# CosmoLink_Alpha_V0_00.net
KiCad netlist of a schematic drawn in Altium Designer
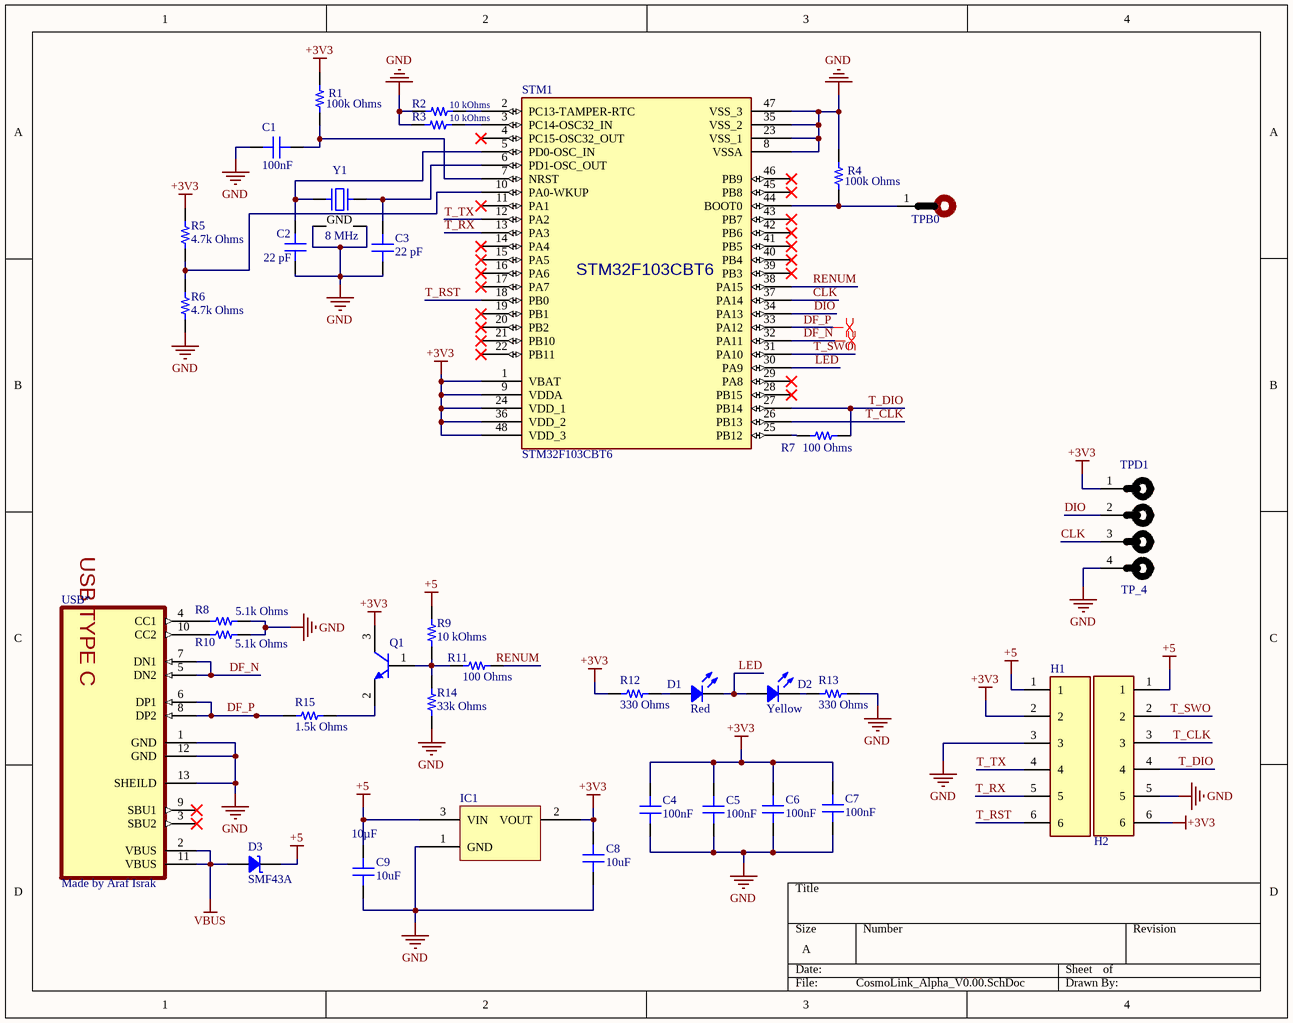
[diagram p0: CosmoLink_Alpha_V0.00.SchDoc]

(export (version "E")
  (design (tool "Eeschema 10.0.6"))
  (components
    (comp (ref "C1")
      (value "0.1µF")
      (footprint "CAP 0603_1608")
      (description "CAP CER 0.1UF 100V X7R 0603")
      (fields
        (field (name "PART NUMBER") "06031C104KAT2A")
        (field (name "CAPACITANCE") "100nF")
        (field (name "MANUFACTURER") "AVX Corporation")
      )
      (libsource (lib "Celestial Altium Library - altium_library") (part "Capacitor"))
    )
    (comp (ref "C2")
      (value "22 pF")
      (footprint "CAP 0603_1608")
      (description "HIGH-Q MLCC (CF): 0603, 22 PF (1")
      (fields
        (field (name "PART NUMBER") "C06CF220F-9ZN-X0T")
        (field (name "CAPACITANCE") "22 pF")
        (field (name "MANUFACTURER") "Knowles Dielectric Labs")
      )
      (libsource (lib "Celestial Altium Library - altium_library") (part "Capacitor"))
    )
    (comp (ref "C3")
      (value "22 pF")
      (footprint "CAP 0603_1608")
      (description "HIGH-Q MLCC (CF): 0603, 22 PF (1")
      (fields
        (field (name "PART NUMBER") "C06CF220F-9ZN-X0T")
        (field (name "CAPACITANCE") "22 pF")
        (field (name "MANUFACTURER") "Knowles Dielectric Labs")
      )
      (libsource (lib "Celestial Altium Library - altium_library") (part "Capacitor"))
    )
    (comp (ref "C4")
      (value "0.1µF")
      (footprint "CAP 0603_1608")
      (description "CAP CER 0.1UF 100V X7R 0603")
      (fields
        (field (name "PART NUMBER") "06031C104KAT2A")
        (field (name "CAPACITANCE") "100nF")
        (field (name "MANUFACTURER") "AVX Corporation")
      )
      (libsource (lib "Celestial Altium Library - altium_library") (part "Capacitor"))
    )
    (comp (ref "C5")
      (value "0.1µF")
      (footprint "CAP 0603_1608")
      (description "CAP CER 0.1UF 100V X7R 0603")
      (fields
        (field (name "PART NUMBER") "06031C104KAT2A")
        (field (name "CAPACITANCE") "100nF")
        (field (name "MANUFACTURER") "AVX Corporation")
      )
      (libsource (lib "Celestial Altium Library - altium_library") (part "Capacitor"))
    )
    (comp (ref "C6")
      (value "0.1µF")
      (footprint "CAP 0603_1608")
      (description "CAP CER 0.1UF 100V X7R 0603")
      (fields
        (field (name "PART NUMBER") "06031C104KAT2A")
        (field (name "CAPACITANCE") "100nF")
        (field (name "MANUFACTURER") "AVX Corporation")
      )
      (libsource (lib "Celestial Altium Library - altium_library") (part "Capacitor"))
    )
    (comp (ref "C7")
      (value "0.1µF")
      (footprint "CAP 0603_1608")
      (description "CAP CER 0.1UF 100V X7R 0603")
      (fields
        (field (name "PART NUMBER") "06031C104KAT2A")
        (field (name "CAPACITANCE") "100nF")
        (field (name "MANUFACTURER") "AVX Corporation")
      )
      (libsource (lib "Celestial Altium Library - altium_library") (part "Capacitor"))
    )
    (comp (ref "C8")
      (value "10µF")
      (footprint "CAP 0603_1608")
      (description "CAP CER 0.1UF 100V X7R 0603")
      (fields
        (field (name "PART NUMBER") "06031C104KAT2A")
        (field (name "CAPACITANCE") "10uF")
        (field (name "MANUFACTURER") "AVX Corporation")
      )
      (libsource (lib "Celestial Altium Library - altium_library") (part "Capacitor"))
    )
    (comp (ref "C9")
      (value "10µF")
      (footprint "CAP 0603_1608")
      (description "CAP CER 0.1UF 100V X7R 0603")
      (fields
        (field (name "PART NUMBER") "06031C104KAT2A")
        (field (name "CAPACITANCE") "10uF")
        (field (name "MANUFACTURER") "AVX Corporation")
      )
      (libsource (lib "Celestial Altium Library - altium_library") (part "Capacitor"))
    )
    (comp (ref "D1")
      (value "Red")
      (footprint "LED 0603_1608 RED")
      (description "LED RED DIFFUSED 1608 SMD")
      (fields
        (field (name "PART NUMBER") "VFHR1111C-3BY2A-TR")
        (field (name "MANUFACTURER") "Stanley Electric Co")
      )
      (libsource (lib "Celestial Altium Library - altium_library") (part "LED"))
    )
    (comp (ref "D2")
      (value "Yellow")
      (footprint "LED 0603_1608 YELLOW")
      (description "LED YELLOW 0603 SMD")
      (fields (field (name "PART NUMBER") "5973405507F") (field (name "MANUFACTURER") "Dialight"))
      (libsource (lib "Celestial Altium Library - altium_library") (part "LED"))
    )
    (comp (ref "D3")
      (value "SMF43A")
      (footprint "SOD123F")
      (description "TVS SOD123FL 43V 200W UNIDIR")
      (fields (field (name "MANUFACTURER") "Littelfuse Inc."))
      (libsource (lib "Celestial Altium Library - altium_library") (part "DIODE TVS UNI"))
    )
    (comp (ref "H1")
      (value "2.54mm_TH_1x6_pin_header")
      (footprint "2.54mm_TH_1x6_pin_header")
      (libsource (lib "Pin_Header_Series_SCH_Library_ARAF") (part "2.54mm_TH_1x6_pin_header"))
    )
    (comp (ref "H2")
      (value "2.54mm_TH_1x6_pin_header")
      (footprint "2.54mm_TH_1x6_pin_header")
      (libsource (lib "") (part "2.54mm_TH_1x6_pin_header_1"))
    )
    (comp (ref "IC1")
      (value "AP2138N-3.3TRG1")
      (footprint "DIODES SOT-23-3 N")
      (description "IC REG LINEAR 3.3V 250MA SOT23-3")
      (fields (field (name "MANUFACTURER") "Diodes Incorporated"))
      (libsource (lib "Celestial Altium Library - altium_library") (part "Diodes Inc AP2138 3PIN"))
    )
    (comp (ref "Q1")
      (value "DNLS160-7")
      (footprint "DIODES SOT-23-3")
      (description "TRANS NPN 60V 1A SOT23-3")
      (fields (field (name "MANUFACTURER") "Diodes Incorporated"))
      (libsource (lib "Celestial Altium Library - altium_library") (part "DIODES INC NPN SOT-23-3"))
    )
    (comp (ref "R1")
      (value "100k Ohms")
      (footprint "RES 0603_1608")
      (description "RES 10K OHM 0.1% 1/16W 0603")
      (fields
        (field (name "PART NUMBER") "RNCS0603BKE10K0")
        (field (name "MANUFACTURER") "Stackpole Electronics Inc")
      )
      (libsource (lib "Celestial Altium Library - altium_library") (part "Resistor"))
    )
    (comp (ref "R2")
      (value "10 kOhms")
      (footprint "RES 0603_1608")
      (description "RES 10K OHM 0.1% 1/16W 0603")
      (fields
        (field (name "PART NUMBER") "RNCS0603BKE10K0")
        (field (name "MANUFACTURER") "Stackpole Electronics Inc")
      )
      (libsource (lib "Celestial Altium Library - altium_library") (part "Resistor"))
    )
    (comp (ref "R3")
      (value "10 kOhms")
      (footprint "RES 0603_1608")
      (description "RES 10K OHM 0.1% 1/16W 0603")
      (fields
        (field (name "PART NUMBER") "RNCS0603BKE10K0")
        (field (name "MANUFACTURER") "Stackpole Electronics Inc")
      )
      (libsource (lib "Celestial Altium Library - altium_library") (part "Resistor"))
    )
    (comp (ref "R4")
      (value "100k Ohms")
      (footprint "RES 0603_1608")
      (description "RES 10K OHM 0.1% 1/16W 0603")
      (fields
        (field (name "PART NUMBER") "RNCS0603BKE10K0")
        (field (name "MANUFACTURER") "Stackpole Electronics Inc")
      )
      (libsource (lib "Celestial Altium Library - altium_library") (part "Resistor"))
    )
    (comp (ref "R5")
      (value "4.7k Ohms")
      (footprint "RES 0603_1608")
      (description "RES 10K OHM 0.1% 1/16W 0603")
      (fields
        (field (name "PART NUMBER") "RNCS0603BKE10K0")
        (field (name "MANUFACTURER") "Stackpole Electronics Inc")
      )
      (libsource (lib "Celestial Altium Library - altium_library") (part "Resistor"))
    )
    (comp (ref "R6")
      (value "4.7k Ohms")
      (footprint "RES 0603_1608")
      (description "RES 10K OHM 0.1% 1/16W 0603")
      (fields
        (field (name "PART NUMBER") "RNCS0603BKE10K0")
        (field (name "MANUFACTURER") "Stackpole Electronics Inc")
      )
      (libsource (lib "Celestial Altium Library - altium_library") (part "Resistor"))
    )
    (comp (ref "R7")
      (value "100 Ohms")
      (footprint "RES 0603_1608")
      (description "RES 10K OHM 0.1% 1/16W 0603")
      (fields
        (field (name "PART NUMBER") "RNCS0603BKE10K0")
        (field (name "MANUFACTURER") "Stackpole Electronics Inc")
      )
      (libsource (lib "Celestial Altium Library - altium_library") (part "Resistor"))
    )
    (comp (ref "R8")
      (value "5.1k Ohms")
      (footprint "RES 0603_1608")
      (description "RES 10K OHM 0.1% 1/16W 0603")
      (fields
        (field (name "PART NUMBER") "RNCS0603BKE10K0")
        (field (name "MANUFACTURER") "Stackpole Electronics Inc")
      )
      (libsource (lib "Celestial Altium Library - altium_library") (part "Resistor"))
    )
    (comp (ref "R9")
      (value "10 kOhms")
      (footprint "RES 0603_1608")
      (description "RES 10K OHM 0.1% 1/16W 0603")
      (fields
        (field (name "PART NUMBER") "RNCS0603BKE10K0")
        (field (name "MANUFACTURER") "Stackpole Electronics Inc")
      )
      (libsource (lib "Celestial Altium Library - altium_library") (part "Resistor"))
    )
    (comp (ref "R10")
      (value "5.1k Ohms")
      (footprint "RES 0603_1608")
      (description "RES 10K OHM 0.1% 1/16W 0603")
      (fields
        (field (name "PART NUMBER") "RNCS0603BKE10K0")
        (field (name "MANUFACTURER") "Stackpole Electronics Inc")
      )
      (libsource (lib "Celestial Altium Library - altium_library") (part "Resistor"))
    )
    (comp (ref "R11")
      (value "100 Ohms")
      (footprint "RES 0603_1608")
      (description "RES 10K OHM 0.1% 1/16W 0603")
      (fields
        (field (name "PART NUMBER") "RNCS0603BKE10K0")
        (field (name "MANUFACTURER") "Stackpole Electronics Inc")
      )
      (libsource (lib "Celestial Altium Library - altium_library") (part "Resistor"))
    )
    (comp (ref "R12")
      (value "330 Ohms")
      (footprint "RES 0603_1608")
      (description "RES 10K OHM 0.1% 1/16W 0603")
      (fields
        (field (name "PART NUMBER") "RNCS0603BKE10K0")
        (field (name "MANUFACTURER") "Stackpole Electronics Inc")
      )
      (libsource (lib "Celestial Altium Library - altium_library") (part "Resistor"))
    )
    (comp (ref "R13")
      (value "330 Ohms")
      (footprint "RES 0603_1608")
      (description "RES 10K OHM 0.1% 1/16W 0603")
      (fields
        (field (name "PART NUMBER") "RNCS0603BKE10K0")
        (field (name "MANUFACTURER") "Stackpole Electronics Inc")
      )
      (libsource (lib "Celestial Altium Library - altium_library") (part "Resistor"))
    )
    (comp (ref "R14")
      (value "33k Ohms")
      (footprint "RES 0603_1608")
      (description "RES 10K OHM 0.1% 1/16W 0603")
      (fields
        (field (name "PART NUMBER") "RNCS0603BKE10K0")
        (field (name "MANUFACTURER") "Stackpole Electronics Inc")
      )
      (libsource (lib "Celestial Altium Library - altium_library") (part "Resistor"))
    )
    (comp (ref "R15")
      (value "1.5k Ohms")
      (footprint "RES 0603_1608")
      (description "RES 10K OHM 0.1% 1/16W 0603")
      (fields
        (field (name "PART NUMBER") "RNCS0603BKE10K0")
        (field (name "MANUFACTURER") "Stackpole Electronics Inc")
      )
      (libsource (lib "Celestial Altium Library - altium_library") (part "Resistor"))
    )
    (comp (ref "STM1")
      (value "STM32F103CBT6")
      (footprint "STM32F103CBT6_FOOTPRINT")
      (description "128KB 2V~3.6V ARM-M3 20KB 72MHz FLASH 37 LQFP-48(7x7) Microcontrollers (MCU/MPU/SOC) ROHS")
      (fields (field (name "JLCPCB PART #") "C8304"))
      (libsource (lib "ARAF_PERSONAL_INTEGRATED_LIBRARY") (part "STM32F103CBT6"))
    )
    (comp (ref "TPB0") (value "TP_1") (footprint "TP1") (libsource (lib "Schlib1") (part "TP_1")))
    (comp (ref "TPD1") (value "TP_4") (footprint "TP4") (libsource (lib "Schlib1") (part "TP_4")))
    (comp (ref "USB*")
      (value "Made by Araf Israk")
      (footprint "USB TYPE-C 24P SMD")
      (fields (field (name "LCSC PART") "C2765186"))
      (libsource (lib "USB_Connector_Series_SCH_Library_ARAF") (part "USB TYPE-C 24P SMD"))
    )
    (comp (ref "Y1")
      (value "8 MHz")
      (footprint "EPSON TSX-3225")
      (description "CRYSTAL 16.0000MHZ 16PF SMD")
      (fields (field (name "PART NUMBER") "TSX-3225 16.0000MF10U-B0") (field (name "MANUFACTURER") "EPSON"))
      (libsource (lib "Celestial Altium Library - altium_library") (part "Epson Crystal TSX-3225"))
    )
  )
  (nets
    (net (code "1") (name "+3V3") (class "Default")
      (node (ref "C4") (pin "2") (pinfunction "2_2") (pintype "passive"))
      (node (ref "C5") (pin "2") (pinfunction "2_2") (pintype "passive"))
      (node (ref "C6") (pin "2") (pinfunction "2_2") (pintype "passive"))
      (node (ref "C7") (pin "2") (pinfunction "2_2") (pintype "passive"))
      (node (ref "C8") (pin "2") (pinfunction "2_2") (pintype "passive"))
      (node (ref "H1") (pin "2") (pinfunction "2_2") (pintype "passive"))
      (node (ref "H2") (pin "6") (pinfunction "6_6") (pintype "passive"))
      (node (ref "IC1") (pin "2") (pinfunction "VOUT_2") (pintype "passive"))
      (node (ref "Q1") (pin "3") (pinfunction "C_3") (pintype "passive"))
      (node (ref "R1") (pin "1") (pinfunction "1_1") (pintype "passive"))
      (node (ref "R12") (pin "1") (pinfunction "1_1") (pintype "passive"))
      (node (ref "R5") (pin "2") (pinfunction "2_2") (pintype "passive"))
      (node (ref "STM1") (pin "1") (pinfunction "VBAT_1") (pintype "power_in"))
      (node (ref "STM1") (pin "24") (pinfunction "VDD_1_24") (pintype "power_in"))
      (node (ref "STM1") (pin "36") (pinfunction "VDD_2_36") (pintype "power_in"))
      (node (ref "STM1") (pin "48") (pinfunction "VDD_3_48") (pintype "power_in"))
      (node (ref "STM1") (pin "9") (pinfunction "VDDA_9") (pintype "power_in"))
      (node (ref "TPD1") (pin "1") (pinfunction "TP1_1") (pintype "passive"))
    )
    (net (code "2") (name "+5") (class "Default")
      (node (ref "C9") (pin "2") (pinfunction "2_2") (pintype "passive"))
      (node (ref "D3") (pin "2") (pinfunction "2_2") (pintype "passive"))
      (node (ref "H1") (pin "1") (pinfunction "1_1") (pintype "passive"))
      (node (ref "H2") (pin "1") (pinfunction "1_1") (pintype "passive"))
      (node (ref "IC1") (pin "3") (pinfunction "VIN_3") (pintype "passive"))
      (node (ref "R9") (pin "2") (pinfunction "2_2") (pintype "passive"))
    )
    (net (code "3") (name "/CLK") (class "Default")
      (node (ref "STM1") (pin "37") (pinfunction "PA14_37") (pintype "bidirectional"))
      (node (ref "TPD1") (pin "3") (pinfunction "TP3_3") (pintype "passive"))
    )
    (net (code "4") (name "/DF_N") (class "Default")
      (node (ref "STM1") (pin "32") (pinfunction "PA11_32") (pintype "bidirectional"))
      (node (ref "USB*") (pin "5") (pinfunction "DN2_5") (pintype "input"))
      (node (ref "USB*") (pin "7") (pinfunction "DN1_7") (pintype "input"))
    )
    (net (code "5") (name "/DF_P") (class "Default")
      (node (ref "R15") (pin "1") (pinfunction "1_1") (pintype "passive"))
      (node (ref "STM1") (pin "33") (pinfunction "PA12_33") (pintype "bidirectional"))
      (node (ref "USB*") (pin "6") (pinfunction "DP1_6") (pintype "input"))
      (node (ref "USB*") (pin "8") (pinfunction "DP2_8") (pintype "input"))
    )
    (net (code "6") (name "/DIO") (class "Default")
      (node (ref "STM1") (pin "34") (pinfunction "PA13_34") (pintype "bidirectional"))
      (node (ref "TPD1") (pin "2") (pinfunction "TP2_2") (pintype "passive"))
    )
    (net (code "7") (name "/LED") (class "Default")
      (node (ref "D1") (pin "2") (pinfunction "2_2") (pintype "passive"))
      (node (ref "D2") (pin "1") (pinfunction "1_1") (pintype "passive"))
      (node (ref "STM1") (pin "30") (pinfunction "PA9_30") (pintype "bidirectional"))
    )
    (net (code "8") (name "/RENUM") (class "Default")
      (node (ref "R11") (pin "2") (pinfunction "2_2") (pintype "passive"))
      (node (ref "STM1") (pin "38") (pinfunction "PA15_38") (pintype "bidirectional"))
    )
    (net (code "9") (name "/T_CLK") (class "Default")
      (node (ref "H2") (pin "3") (pinfunction "3_3") (pintype "passive"))
      (node (ref "STM1") (pin "26") (pinfunction "PB13_26") (pintype "bidirectional"))
    )
    (net (code "10") (name "/T_DIO") (class "Default")
      (node (ref "H2") (pin "4") (pinfunction "4_4") (pintype "passive"))
      (node (ref "R7") (pin "2") (pinfunction "2_2") (pintype "passive"))
      (node (ref "STM1") (pin "27") (pinfunction "PB14_27") (pintype "bidirectional"))
    )
    (net (code "11") (name "/T_RST") (class "Default")
      (node (ref "H1") (pin "6") (pinfunction "6_6") (pintype "passive"))
      (node (ref "STM1") (pin "18") (pinfunction "PB0_18") (pintype "bidirectional"))
    )
    (net (code "12") (name "/T_RX") (class "Default")
      (node (ref "H1") (pin "5") (pinfunction "5_5") (pintype "passive"))
      (node (ref "STM1") (pin "13") (pinfunction "PA3_13") (pintype "bidirectional"))
    )
    (net (code "13") (name "/T_SWO") (class "Default")
      (node (ref "H2") (pin "2") (pinfunction "2_2") (pintype "passive"))
      (node (ref "STM1") (pin "31") (pinfunction "PA10_31") (pintype "bidirectional"))
    )
    (net (code "14") (name "/T_TX") (class "Default")
      (node (ref "H1") (pin "4") (pinfunction "4_4") (pintype "passive"))
      (node (ref "STM1") (pin "12") (pinfunction "PA2_12") (pintype "bidirectional"))
    )
    (net (code "15") (name "GND") (class "Default")
      (node (ref "C1") (pin "1") (pinfunction "1_1") (pintype "passive"))
      (node (ref "C2") (pin "1") (pinfunction "1_1") (pintype "passive"))
      (node (ref "C3") (pin "1") (pinfunction "1_1") (pintype "passive"))
      (node (ref "C4") (pin "1") (pinfunction "1_1") (pintype "passive"))
      (node (ref "C5") (pin "1") (pinfunction "1_1") (pintype "passive"))
      (node (ref "C6") (pin "1") (pinfunction "1_1") (pintype "passive"))
      (node (ref "C7") (pin "1") (pinfunction "1_1") (pintype "passive"))
      (node (ref "C8") (pin "1") (pinfunction "1_1") (pintype "passive"))
      (node (ref "C9") (pin "1") (pinfunction "1_1") (pintype "passive"))
      (node (ref "H1") (pin "3") (pinfunction "3_3") (pintype "passive"))
      (node (ref "H2") (pin "5") (pinfunction "5_5") (pintype "passive"))
      (node (ref "IC1") (pin "1") (pinfunction "GND_1") (pintype "passive"))
      (node (ref "R10") (pin "2") (pinfunction "2_2") (pintype "passive"))
      (node (ref "R13") (pin "2") (pinfunction "2_2") (pintype "passive"))
      (node (ref "R14") (pin "1") (pinfunction "1_1") (pintype "passive"))
      (node (ref "R2") (pin "1") (pinfunction "1_1") (pintype "passive"))
      (node (ref "R3") (pin "1") (pinfunction "1_1") (pintype "passive"))
      (node (ref "R4") (pin "1") (pinfunction "1_1") (pintype "passive"))
      (node (ref "R6") (pin "1") (pinfunction "1_1") (pintype "passive"))
      (node (ref "R8") (pin "2") (pinfunction "2_2") (pintype "passive"))
      (node (ref "STM1") (pin "23") (pinfunction "VSS_1_23") (pintype "power_in"))
      (node (ref "STM1") (pin "35") (pinfunction "VSS_2_35") (pintype "power_in"))
      (node (ref "STM1") (pin "47") (pinfunction "VSS_3_47") (pintype "power_in"))
      (node (ref "STM1") (pin "8") (pinfunction "VSSA_8") (pintype "power_in"))
      (node (ref "TPD1") (pin "4") (pinfunction "TP4_4") (pintype "passive"))
      (node (ref "USB*") (pin "1") (pinfunction "GND_1") (pintype "power_in"))
      (node (ref "USB*") (pin "12") (pinfunction "GND_12") (pintype "power_in"))
      (node (ref "USB*") (pin "13") (pinfunction "SHEILD_13") (pintype "passive"))
      (node (ref "Y1") (pin "2") (pinfunction "GND_2") (pintype "passive"))
      (node (ref "Y1") (pin "4") (pinfunction "GND_4") (pintype "passive"))
    )
    (net (code "16") (name "Net-(D1-Pad1)") (class "Default")
      (node (ref "D1") (pin "1") (pinfunction "1_1") (pintype "passive"))
      (node (ref "R12") (pin "2") (pinfunction "2_2") (pintype "passive"))
    )
    (net (code "17") (name "Net-(D2-Pad2)") (class "Default")
      (node (ref "D2") (pin "2") (pinfunction "2_2") (pintype "passive"))
      (node (ref "R13") (pin "1") (pinfunction "1_1") (pintype "passive"))
    )
    (net (code "18") (name "Net-(Q1-B)") (class "Default")
      (node (ref "Q1") (pin "1") (pinfunction "B_1") (pintype "passive"))
      (node (ref "R11") (pin "1") (pinfunction "1_1") (pintype "passive"))
      (node (ref "R14") (pin "2") (pinfunction "2_2") (pintype "passive"))
      (node (ref "R9") (pin "1") (pinfunction "1_1") (pintype "passive"))
    )
    (net (code "19") (name "Net-(Q1-E)") (class "Default")
      (node (ref "Q1") (pin "2") (pinfunction "E_2") (pintype "passive"))
      (node (ref "R15") (pin "2") (pinfunction "2_2") (pintype "passive"))
    )
    (net (code "20") (name "Net-(STM1-BOOT0)") (class "Default")
      (node (ref "R4") (pin "2") (pinfunction "2_2") (pintype "passive"))
      (node (ref "STM1") (pin "44") (pinfunction "BOOT0_44") (pintype "bidirectional"))
      (node (ref "TPB0") (pin "1") (pinfunction "TP1_1") (pintype "passive"))
    )
    (net (code "21") (name "Net-(STM1-NRST)") (class "Default")
      (node (ref "C1") (pin "2") (pinfunction "2_2") (pintype "passive"))
      (node (ref "R1") (pin "2") (pinfunction "2_2") (pintype "passive"))
      (node (ref "STM1") (pin "7") (pinfunction "NRST_7") (pintype "bidirectional"))
    )
    (net (code "22") (name "Net-(STM1-PA0-WKUP)") (class "Default")
      (node (ref "R5") (pin "1") (pinfunction "1_1") (pintype "passive"))
      (node (ref "R6") (pin "2") (pinfunction "2_2") (pintype "passive"))
      (node (ref "STM1") (pin "10") (pinfunction "PA0-WKUP_10") (pintype "bidirectional"))
    )
    (net (code "23") (name "Net-(STM1-PB12)") (class "Default")
      (node (ref "R7") (pin "1") (pinfunction "1_1") (pintype "passive"))
      (node (ref "STM1") (pin "25") (pinfunction "PB12_25") (pintype "bidirectional"))
    )
    (net (code "24") (name "Net-(STM1-PC13-TAMPER-RTC)") (class "Default")
      (node (ref "R2") (pin "2") (pinfunction "2_2") (pintype "passive"))
      (node (ref "STM1") (pin "2") (pinfunction "PC13-TAMPER-RTC_2") (pintype "bidirectional"))
    )
    (net (code "25") (name "Net-(STM1-PC14-OSC32_IN)") (class "Default")
      (node (ref "R3") (pin "2") (pinfunction "2_2") (pintype "passive"))
      (node (ref "STM1") (pin "3") (pinfunction "PC14-OSC32_IN_3") (pintype "bidirectional"))
    )
    (net (code "26") (name "Net-(STM1-PD0-OSC_IN)") (class "Default")
      (node (ref "C2") (pin "2") (pinfunction "2_2") (pintype "passive"))
      (node (ref "STM1") (pin "5") (pinfunction "PD0-OSC_IN_5") (pintype "bidirectional"))
      (node (ref "Y1") (pin "1") (pinfunction "1_1") (pintype "passive"))
    )
    (net (code "27") (name "Net-(STM1-PD1-OSC_OUT)") (class "Default")
      (node (ref "C3") (pin "2") (pinfunction "2_2") (pintype "passive"))
      (node (ref "STM1") (pin "6") (pinfunction "PD1-OSC_OUT_6") (pintype "bidirectional"))
      (node (ref "Y1") (pin "3") (pinfunction "3_3") (pintype "passive"))
    )
    (net (code "28") (name "Net-(USB*-CC1)") (class "Default")
      (node (ref "R8") (pin "1") (pinfunction "1_1") (pintype "passive"))
      (node (ref "USB*") (pin "4") (pinfunction "CC1_4") (pintype "output"))
    )
    (net (code "29") (name "Net-(USB*-CC2)") (class "Default")
      (node (ref "R10") (pin "1") (pinfunction "1_1") (pintype "passive"))
      (node (ref "USB*") (pin "10") (pinfunction "CC2_10") (pintype "output"))
    )
    (net (code "30") (name "VBUS") (class "Default")
      (node (ref "D3") (pin "1") (pinfunction "1_1") (pintype "passive"))
      (node (ref "USB*") (pin "11") (pinfunction "VBUS_11") (pintype "power_in"))
      (node (ref "USB*") (pin "2") (pinfunction "VBUS_2") (pintype "power_in"))
    )
    (net (code "31") (name "unconnected-(STM1-PA1-Pad11)") (class "Default")
      (node (ref "STM1") (pin "11") (pinfunction "PA1_11") (pintype "bidirectional+no_connect"))
    )
    (net (code "32") (name "unconnected-(STM1-PA4-Pad14)") (class "Default")
      (node (ref "STM1") (pin "14") (pinfunction "PA4_14") (pintype "bidirectional+no_connect"))
    )
    (net (code "33") (name "unconnected-(STM1-PA5-Pad15)") (class "Default")
      (node (ref "STM1") (pin "15") (pinfunction "PA5_15") (pintype "bidirectional+no_connect"))
    )
    (net (code "34") (name "unconnected-(STM1-PA6-Pad16)") (class "Default")
      (node (ref "STM1") (pin "16") (pinfunction "PA6_16") (pintype "bidirectional+no_connect"))
    )
    (net (code "35") (name "unconnected-(STM1-PA7-Pad17)") (class "Default")
      (node (ref "STM1") (pin "17") (pinfunction "PA7_17") (pintype "bidirectional+no_connect"))
    )
    (net (code "36") (name "unconnected-(STM1-PA8-Pad29)") (class "Default")
      (node (ref "STM1") (pin "29") (pinfunction "PA8_29") (pintype "bidirectional+no_connect"))
    )
    (net (code "37") (name "unconnected-(STM1-PB1-Pad19)") (class "Default")
      (node (ref "STM1") (pin "19") (pinfunction "PB1_19") (pintype "bidirectional+no_connect"))
    )
    (net (code "38") (name "unconnected-(STM1-PB2-Pad20)") (class "Default")
      (node (ref "STM1") (pin "20") (pinfunction "PB2_20") (pintype "bidirectional+no_connect"))
    )
    (net (code "39") (name "unconnected-(STM1-PB3-Pad39)") (class "Default")
      (node (ref "STM1") (pin "39") (pinfunction "PB3_39") (pintype "bidirectional+no_connect"))
    )
    (net (code "40") (name "unconnected-(STM1-PB4-Pad40)") (class "Default")
      (node (ref "STM1") (pin "40") (pinfunction "PB4_40") (pintype "bidirectional+no_connect"))
    )
    (net (code "41") (name "unconnected-(STM1-PB5-Pad41)") (class "Default")
      (node (ref "STM1") (pin "41") (pinfunction "PB5_41") (pintype "bidirectional+no_connect"))
    )
    (net (code "42") (name "unconnected-(STM1-PB6-Pad42)") (class "Default")
      (node (ref "STM1") (pin "42") (pinfunction "PB6_42") (pintype "bidirectional+no_connect"))
    )
    (net (code "43") (name "unconnected-(STM1-PB7-Pad43)") (class "Default")
      (node (ref "STM1") (pin "43") (pinfunction "PB7_43") (pintype "bidirectional+no_connect"))
    )
    (net (code "44") (name "unconnected-(STM1-PB8-Pad45)") (class "Default")
      (node (ref "STM1") (pin "45") (pinfunction "PB8_45") (pintype "bidirectional+no_connect"))
    )
    (net (code "45") (name "unconnected-(STM1-PB9-Pad46)") (class "Default")
      (node (ref "STM1") (pin "46") (pinfunction "PB9_46") (pintype "bidirectional+no_connect"))
    )
    (net (code "46") (name "unconnected-(STM1-PB10-Pad21)") (class "Default")
      (node (ref "STM1") (pin "21") (pinfunction "PB10_21") (pintype "bidirectional+no_connect"))
    )
    (net (code "47") (name "unconnected-(STM1-PB11-Pad22)") (class "Default")
      (node (ref "STM1") (pin "22") (pinfunction "PB11_22") (pintype "bidirectional+no_connect"))
    )
    (net (code "48") (name "unconnected-(STM1-PB15-Pad28)") (class "Default")
      (node (ref "STM1") (pin "28") (pinfunction "PB15_28") (pintype "bidirectional+no_connect"))
    )
    (net (code "49") (name "unconnected-(STM1-PC15-OSC32_OUT-Pad4)") (class "Default")
      (node (ref "STM1") (pin "4") (pinfunction "PC15-OSC32_OUT_4") (pintype "bidirectional+no_connect"))
    )
    (net (code "50") (name "unconnected-(USB*-SBU1-Pad9)") (class "Default")
      (node (ref "USB*") (pin "9") (pinfunction "SBU1_9") (pintype "output+no_connect"))
    )
    (net (code "51") (name "unconnected-(USB*-SBU2-Pad3)") (class "Default")
      (node (ref "USB*") (pin "3") (pinfunction "SBU2_3") (pintype "output+no_connect"))
    )
  )
)
